# dcb_lite_adc.net
KiCad netlist of a schematic drawn in Altium Designer
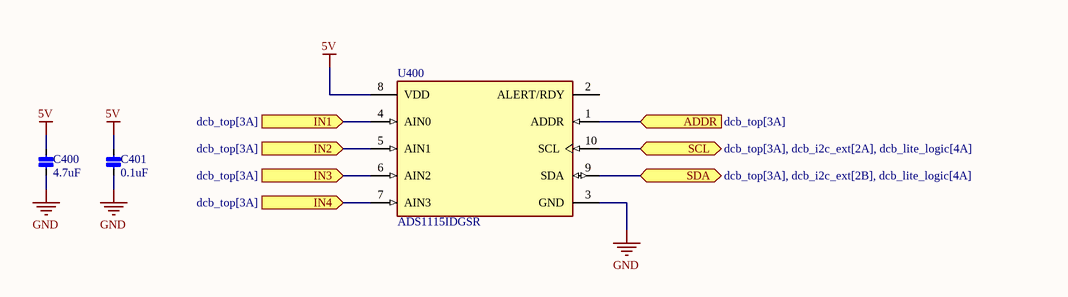
[diagram p0: dcb_lite_adc.SchDoc]

(export (version "E")
  (design (tool "Eeschema 10.0.6"))
  (components
    (comp (ref "C400")
      (value "4.7uF")
      (footprint "FP-CL10-IPC_C")
      (description "Cap Ceramic 4.7uF 6.3V X7R 10% SMD 0603 125°C Paper T/R")
      (fields (field (name "Comment") "CAP 4.7uF 0603 6.3V X7R"))
      (libsource (lib "StackFoundry LLC") (part "C-EU"))
    )
    (comp (ref "C401")
      (value "0.1uF")
      (footprint "FP-CL10-IPC_B")
      (description "Cap Ceramic 0.1uF 50V X7R 20% SMD 0603 125C Paper T/R")
      (fields (field (name "VOLTAGE") "50V") (field (name "Comment") "CAP 0.1uF 50V X7R 0603"))
      (libsource (lib "StackFoundry LLC") (part "C-EU"))
    )
    (comp (ref "U400")
      (value "ADS1115IDGSR")
      (footprint "FP-DGS0010A-MFG")
      (description "4-Channel Single ADC Delta-Sigma 860sps 16-bit Serial 10-Pin VSSOP T/R")
      (libsource (lib "StackFoundry LLC") (part "1442cd67780685bba1a77ae27c88037"))
    )
  )
  (nets
    (net (code "1") (name "/ADDR") (class "Default")
      (node (ref "U400") (pin "1") (pinfunction "ADDR_1") (pintype "input"))
    )
    (net (code "2") (name "/IN1") (class "Default")
      (node (ref "U400") (pin "4") (pinfunction "AIN0_4") (pintype "input"))
    )
    (net (code "3") (name "/IN2") (class "Default")
      (node (ref "U400") (pin "5") (pinfunction "AIN1_5") (pintype "input"))
    )
    (net (code "4") (name "/IN3") (class "Default")
      (node (ref "U400") (pin "6") (pinfunction "AIN2_6") (pintype "input"))
    )
    (net (code "5") (name "/IN4") (class "Default")
      (node (ref "U400") (pin "7") (pinfunction "AIN3_7") (pintype "input"))
    )
    (net (code "6") (name "/SCL") (class "Default")
      (node (ref "U400") (pin "10") (pinfunction "SCL_10") (pintype "input"))
    )
    (net (code "7") (name "/SDA") (class "Default")
      (node (ref "U400") (pin "9") (pinfunction "SDA_9") (pintype "bidirectional"))
    )
    (net (code "8") (name "5V") (class "Default")
      (node (ref "C400") (pin "1") (pinfunction "1_1") (pintype "passive"))
      (node (ref "C401") (pin "1") (pinfunction "1_1") (pintype "passive"))
      (node (ref "U400") (pin "8") (pinfunction "VDD_8") (pintype "power_in"))
    )
    (net (code "9") (name "GND") (class "Default")
      (node (ref "C400") (pin "2") (pinfunction "2_2") (pintype "passive"))
      (node (ref "C401") (pin "2") (pinfunction "2_2") (pintype "passive"))
      (node (ref "U400") (pin "3") (pinfunction "GND_3") (pintype "power_in"))
    )
    (net (code "10") (name "unconnected-(U400-ALERT{slash}RDY-Pad2)") (class "Default")
      (node (ref "U400") (pin "2") (pinfunction "ALERT/RDY_2") (pintype "open_collector"))
    )
  )
)
